# BLDCM.net
KiCad netlist of a schematic drawn in EAGLE
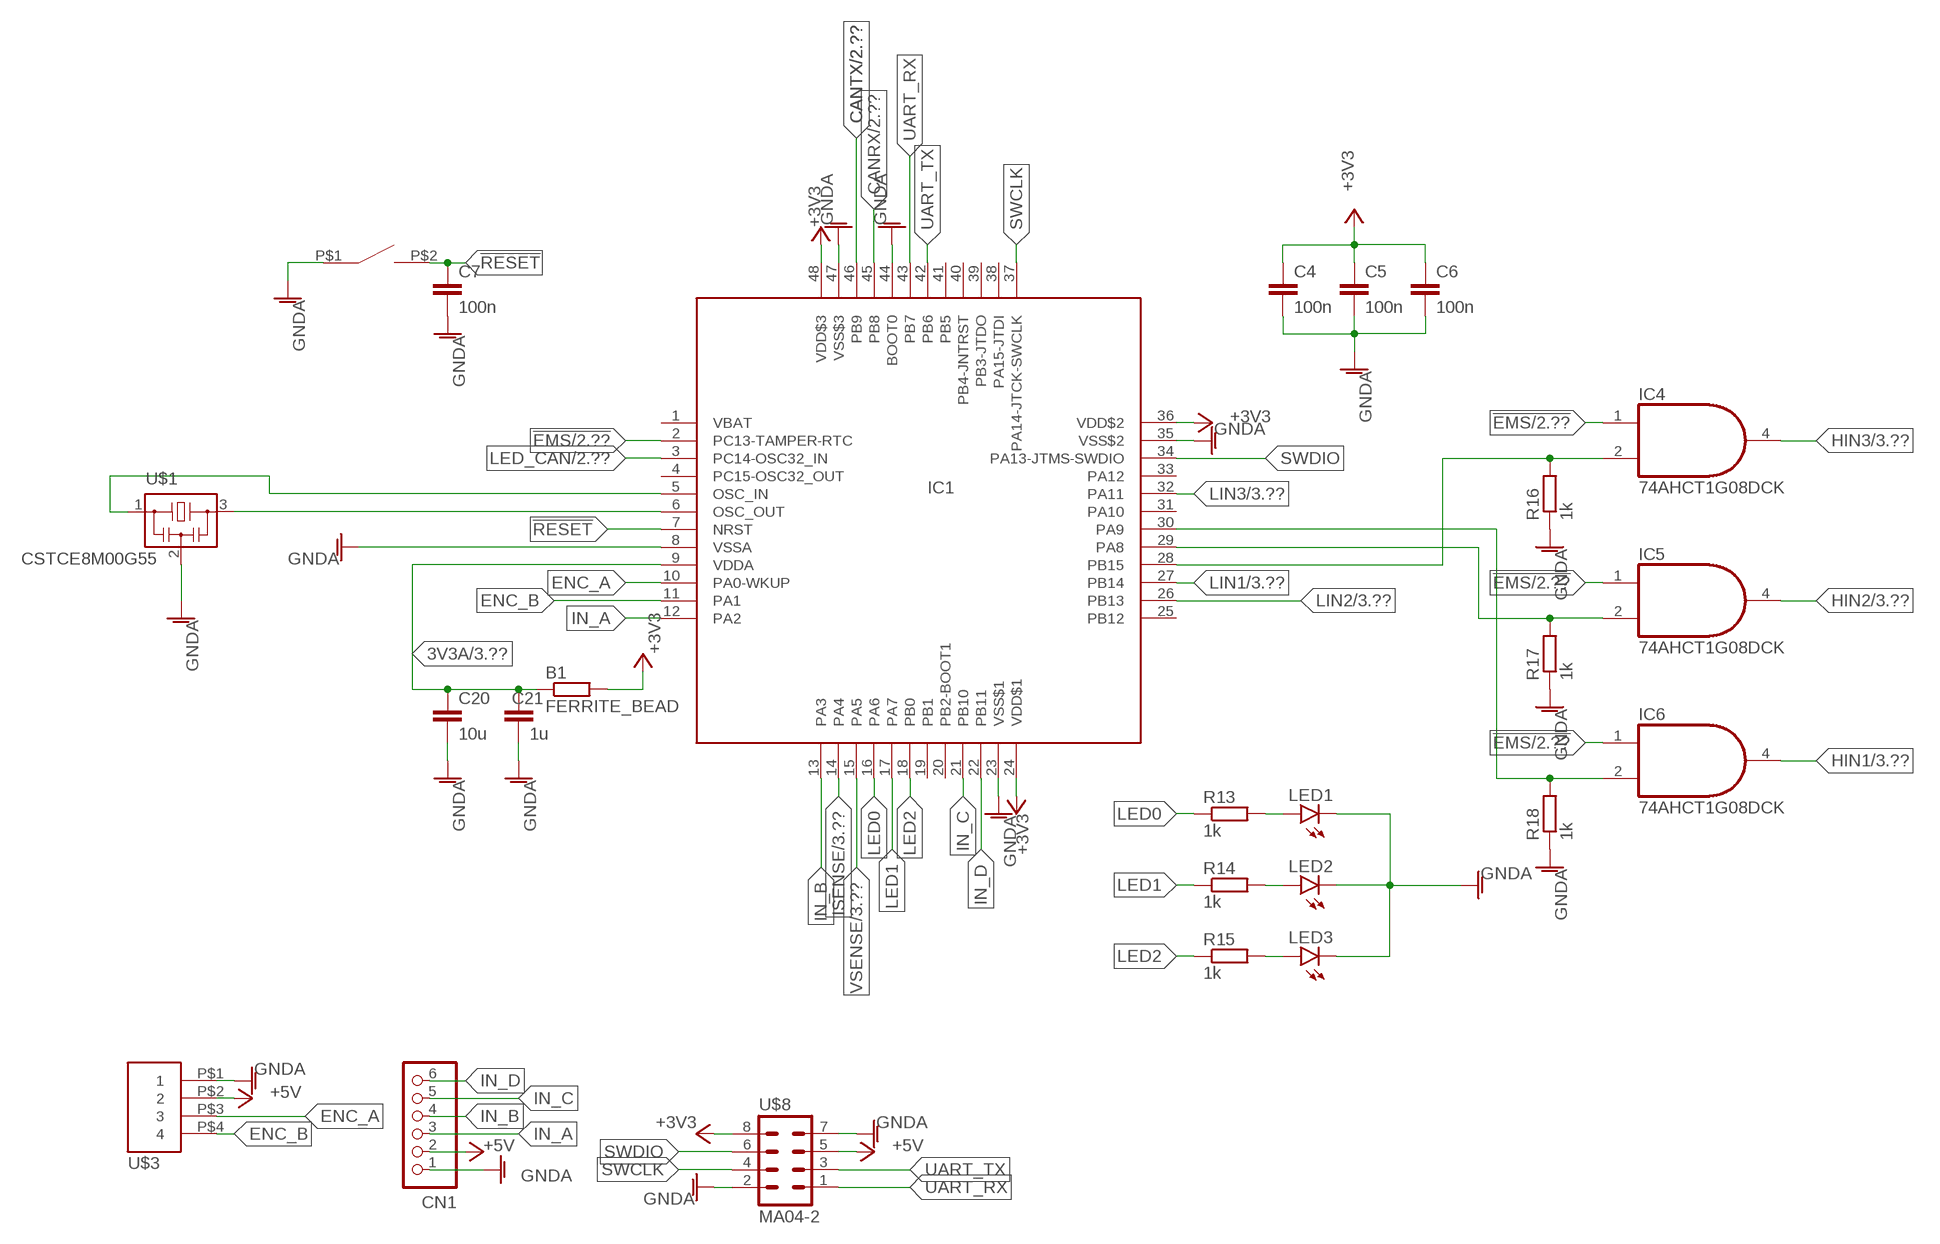
[diagram p0: schematic, sheet 1]
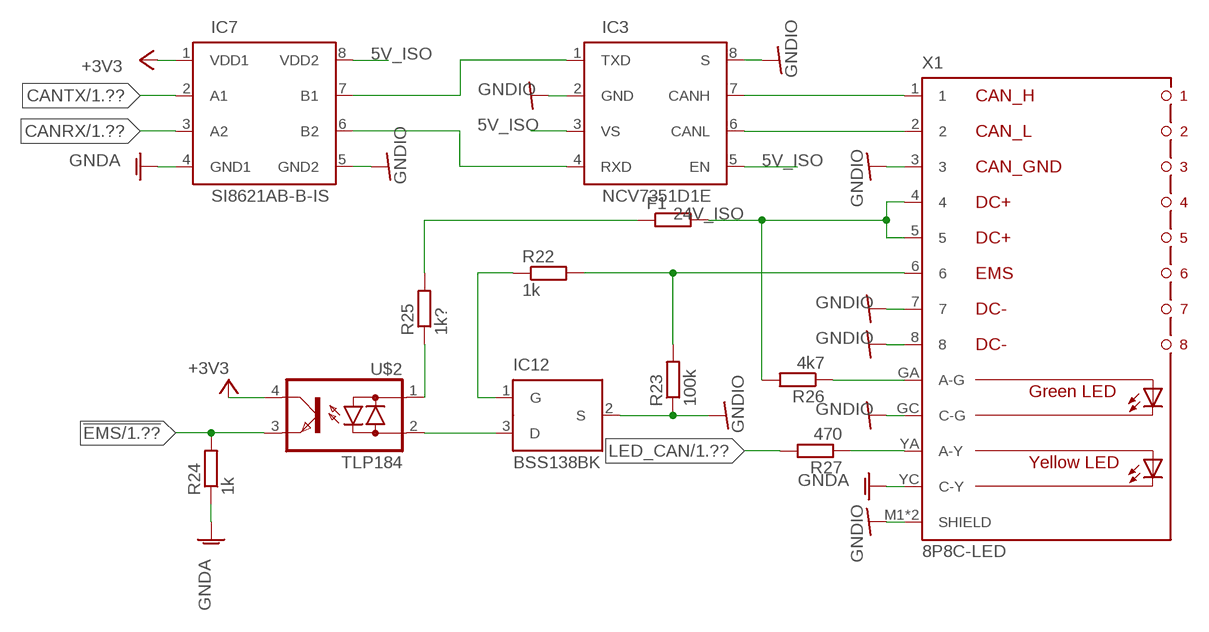
[diagram p1: schematic, sheet 2]
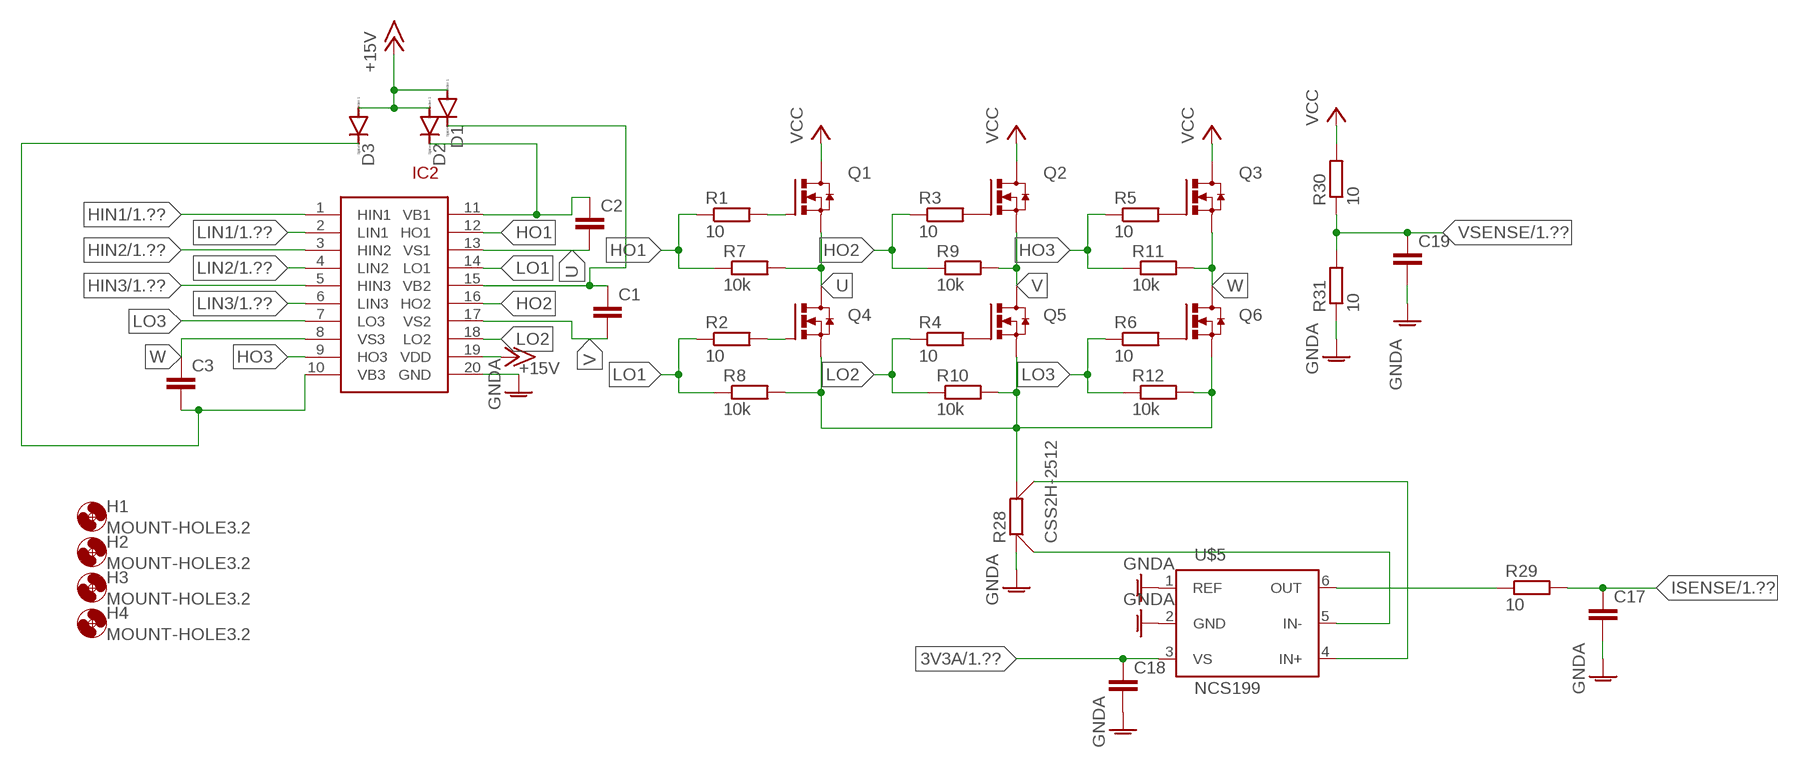
[diagram p2: schematic, sheet 3]
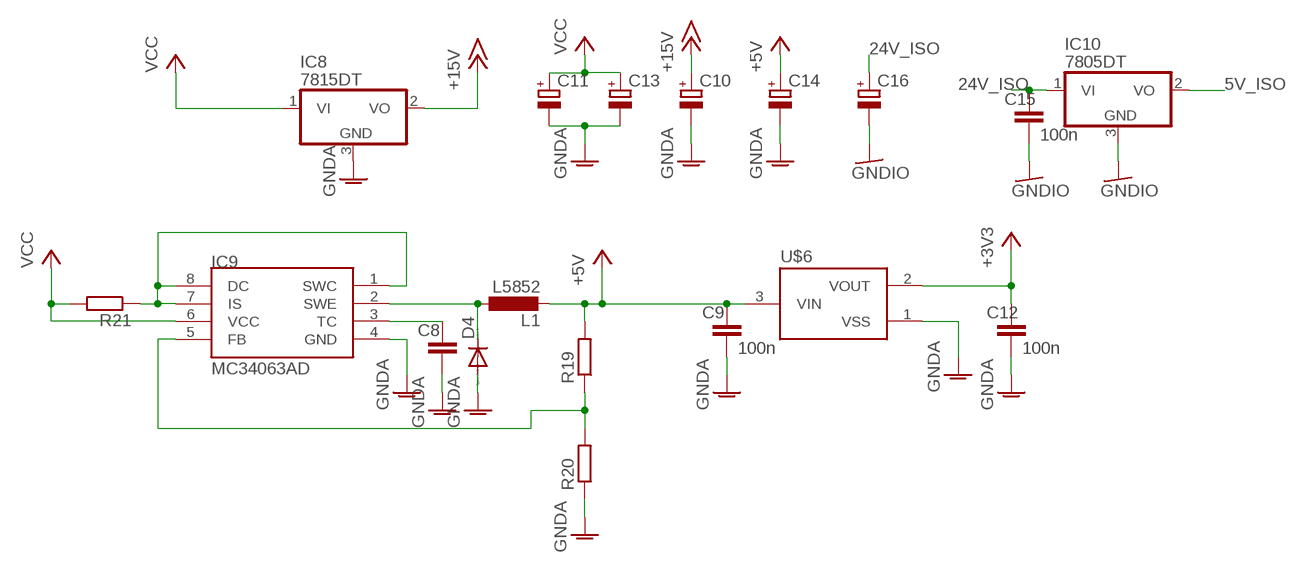
[diagram p3: schematic, sheet 4]

(export (version "E")
  (design (tool "Eeschema 10.0.6"))
  (components
    (comp (ref "C8")
      (value "C-EUC0603")
      (footprint "eagle-import:C0603")
      (libsource (lib "eagle-import") (part "C-EUC0603"))
    )
    (comp (ref "C9")
      (value "100n")
      (footprint "eagle-import:C0603")
      (libsource (lib "eagle-import") (part "C-EUC0603"))
    )
    (comp (ref "C10")
      (value "CPOL-EUE2.5-5")
      (footprint "eagle-import:E2,5-5")
      (libsource (lib "eagle-import") (part "CPOL-EUE2.5-5"))
    )
    (comp (ref "C11")
      (value "CPOL-EUE5-10.5")
      (footprint "eagle-import:E5-10,5")
      (libsource (lib "eagle-import") (part "CPOL-EUE5-10.5"))
    )
    (comp (ref "C12")
      (value "100n")
      (footprint "eagle-import:C0603")
      (libsource (lib "eagle-import") (part "C-EUC0603"))
    )
    (comp (ref "C13")
      (value "CPOL-EUE5-10.5")
      (footprint "eagle-import:E5-10,5")
      (libsource (lib "eagle-import") (part "CPOL-EUE5-10.5"))
    )
    (comp (ref "C14")
      (value "CPOL-EUE2.5-5")
      (footprint "eagle-import:E2,5-5")
      (libsource (lib "eagle-import") (part "CPOL-EUE2.5-5"))
    )
    (comp (ref "C15")
      (value "100n")
      (footprint "eagle-import:C0603")
      (libsource (lib "eagle-import") (part "C-EUC0603"))
    )
    (comp (ref "C16")
      (value "CPOL-EUE2.5-5")
      (footprint "eagle-import:E2,5-5")
      (libsource (lib "eagle-import") (part "CPOL-EUE2.5-5"))
    )
    (comp (ref "D4")
      (value "DIODE-SOD123")
      (footprint "eagle-import:SOD123")
      (libsource (lib "eagle-import") (part "mylib_DIODE-SOD123"))
    )
    (comp (ref "IC8")
      (value "7815DT")
      (footprint "eagle-import:TO252")
      (libsource (lib "eagle-import") (part "78DT24"))
    )
    (comp (ref "IC9")
      (value "MC34063AD")
      (footprint "eagle-import:SOIC8")
      (libsource (lib "eagle-import") (part "MC34063AD"))
    )
    (comp (ref "IC10")
      (value "7805DT")
      (footprint "eagle-import:TO252")
      (libsource (lib "eagle-import") (part "78DT24"))
    )
    (comp (ref "L1")
      (value "L5852")
      (footprint "eagle-import:L5852")
      (libsource (lib "eagle-import") (part "L5852"))
    )
    (comp (ref "R19")
      (value "R-EU_R0603")
      (footprint "eagle-import:R0603")
      (libsource (lib "eagle-import") (part "mylib_R-EU_R0603"))
    )
    (comp (ref "R20")
      (value "R-EU_R0603")
      (footprint "eagle-import:R0603")
      (libsource (lib "eagle-import") (part "mylib_R-EU_R0603"))
    )
    (comp (ref "R21")
      (value "R-EU_R0603")
      (footprint "eagle-import:R0603")
      (libsource (lib "eagle-import") (part "mylib_R-EU_R0603"))
    )
    (comp (ref "U$6")
      (value "XC6206")
      (footprint "eagle-import:SOT95P240X110-3")
      (libsource (lib "eagle-import") (part "XC6206"))
    )
    (comp (ref "B1")
      (value "FERRITE_BEAD")
      (footprint "eagle-import:R0603")
      (libsource (lib "eagle-import") (part "mylib_R-EU_R0603"))
    )
    (comp (ref "C4")
      (value "100n")
      (footprint "eagle-import:C0603")
      (libsource (lib "eagle-import") (part "rcl_334_C-EUC0603"))
    )
    (comp (ref "C5")
      (value "100n")
      (footprint "eagle-import:C0603")
      (libsource (lib "eagle-import") (part "rcl_334_C-EUC0603"))
    )
    (comp (ref "C6")
      (value "100n")
      (footprint "eagle-import:C0603")
      (libsource (lib "eagle-import") (part "rcl_334_C-EUC0603"))
    )
    (comp (ref "C7")
      (value "100n")
      (footprint "eagle-import:C0603")
      (libsource (lib "eagle-import") (part "rcl_334_C-EUC0603"))
    )
    (comp (ref "C20")
      (value "10u")
      (footprint "eagle-import:C0603")
      (libsource (lib "eagle-import") (part "rcl_334_C-EUC0603"))
    )
    (comp (ref "C21")
      (value "1u")
      (footprint "eagle-import:C0603")
      (libsource (lib "eagle-import") (part "rcl_334_C-EUC0603"))
    )
    (comp (ref "CN1")
      (value "S6B-XH-A")
      (footprint "eagle-import:S6B-XH-A")
      (libsource (lib "eagle-import") (part "S6B-XH-A"))
    )
    (comp (ref "IC1")
      (value "STM32F103C8")
      (footprint "eagle-import:LQFP48")
      (libsource (lib "eagle-import") (part "STM32F103C8"))
    )
    (comp (ref "IC4")
      (value "74AHCT1G08DCK")
      (footprint "eagle-import:SC70-5")
      (libsource (lib "eagle-import") (part "741G08DCKAHCT"))
    )
    (comp (ref "IC5")
      (value "74AHCT1G08DCK")
      (footprint "eagle-import:SC70-5")
      (libsource (lib "eagle-import") (part "741G08DCKAHCT"))
    )
    (comp (ref "IC6")
      (value "74AHCT1G08DCK")
      (footprint "eagle-import:SC70-5")
      (libsource (lib "eagle-import") (part "741G08DCKAHCT"))
    )
    (comp (ref "LED1")
      (value "LEDCHIP-LED0805")
      (footprint "eagle-import:CHIP-LED0805")
      (libsource (lib "eagle-import") (part "LEDCHIP-LED0805"))
    )
    (comp (ref "LED2")
      (value "LEDCHIP-LED0805")
      (footprint "eagle-import:CHIP-LED0805")
      (libsource (lib "eagle-import") (part "LEDCHIP-LED0805"))
    )
    (comp (ref "LED3")
      (value "LEDCHIP-LED0805")
      (footprint "eagle-import:CHIP-LED0805")
      (libsource (lib "eagle-import") (part "LEDCHIP-LED0805"))
    )
    (comp (ref "R13")
      (value "1k")
      (footprint "eagle-import:R0603")
      (libsource (lib "eagle-import") (part "mylib_R-EU_R0603"))
    )
    (comp (ref "R14")
      (value "1k")
      (footprint "eagle-import:R0603")
      (libsource (lib "eagle-import") (part "mylib_R-EU_R0603"))
    )
    (comp (ref "R15")
      (value "1k")
      (footprint "eagle-import:R0603")
      (libsource (lib "eagle-import") (part "mylib_R-EU_R0603"))
    )
    (comp (ref "R16")
      (value "1k")
      (footprint "eagle-import:R0603")
      (libsource (lib "eagle-import") (part "mylib_R-EU_R0603"))
    )
    (comp (ref "R17")
      (value "1k")
      (footprint "eagle-import:R0603")
      (libsource (lib "eagle-import") (part "mylib_R-EU_R0603"))
    )
    (comp (ref "R18")
      (value "1k")
      (footprint "eagle-import:R0603")
      (libsource (lib "eagle-import") (part "mylib_R-EU_R0603"))
    )
    (comp (ref "U$1")
      (value "CSTCE8M00G55")
      (footprint "eagle-import:CSTCE8M00G55")
      (libsource (lib "eagle-import") (part "CSTCE8M00G55"))
    )
    (comp (ref "U$3")
      (value "XH-4-SIDE")
      (footprint "eagle-import:CON-XH-4-SIDE")
      (libsource (lib "eagle-import") (part "XH-4-SIDE"))
    )
    (comp (ref "U$4")
      (value "SWITCH_TACTILETOP")
      (footprint "eagle-import:SWITCH_TACTILE_3X6")
      (libsource (lib "eagle-import") (part "SWITCH_TACTILETOP"))
    )
    (comp (ref "U$8")
      (value "MA04-2")
      (footprint "eagle-import:MA04-2W")
      (libsource (lib "eagle-import") (part "MA04-2"))
    )
    (comp (ref "F1")
      (value "R-EU_R1206")
      (footprint "eagle-import:R1206")
      (libsource (lib "eagle-import") (part "R-EU_R1206"))
    )
    (comp (ref "IC3")
      (value "NCV7351D1E")
      (footprint "eagle-import:SO08")
      (libsource (lib "eagle-import") (part "NCV7351D1E"))
    )
    (comp (ref "IC7")
      (value "SI8621AB-B-IS")
      (footprint "eagle-import:SO08")
      (libsource (lib "eagle-import") (part "SI8621AB-B-IS"))
    )
    (comp (ref "IC12")
      (value "BSS138BK")
      (footprint "eagle-import:SOT23")
      (fields (field (name "MF") "MAXIM") (field (name "MPN") "MAX6520EUR-T"))
      (libsource (lib "eagle-import") (part "BSS138BK"))
    )
    (comp (ref "R22")
      (value "1k")
      (footprint "eagle-import:R0603")
      (libsource (lib "eagle-import") (part "mylib_R-EU_R0603"))
    )
    (comp (ref "R23")
      (value "100k")
      (footprint "eagle-import:R0603")
      (libsource (lib "eagle-import") (part "mylib_R-EU_R0603"))
    )
    (comp (ref "R24")
      (value "1k")
      (footprint "eagle-import:R0603")
      (libsource (lib "eagle-import") (part "mylib_R-EU_R0603"))
    )
    (comp (ref "R25")
      (value "1k?")
      (footprint "eagle-import:R0603")
      (libsource (lib "eagle-import") (part "mylib_R-EU_R0603"))
    )
    (comp (ref "R26")
      (value "4k7")
      (footprint "eagle-import:R0603")
      (libsource (lib "eagle-import") (part "mylib_R-EU_R0603"))
    )
    (comp (ref "R27")
      (value "470")
      (footprint "eagle-import:R0603")
      (libsource (lib "eagle-import") (part "mylib_R-EU_R0603"))
    )
    (comp (ref "U$2")
      (value "TLP184")
      (footprint "eagle-import:11-4M1S")
      (libsource (lib "eagle-import") (part "TLP184"))
    )
    (comp (ref "X1")
      (value "8P8C-LED")
      (footprint "eagle-import:8P8C-LED")
      (libsource (lib "eagle-import") (part "8P8C-LED"))
    )
    (comp (ref "C1")
      (value "C-EUC0603")
      (footprint "eagle-import:C0603")
      (libsource (lib "eagle-import") (part "rcl_334_C-EUC0603"))
    )
    (comp (ref "C2")
      (value "C-EUC0603")
      (footprint "eagle-import:C0603")
      (libsource (lib "eagle-import") (part "rcl_334_C-EUC0603"))
    )
    (comp (ref "C3")
      (value "C-EUC0603")
      (footprint "eagle-import:C0603")
      (libsource (lib "eagle-import") (part "rcl_334_C-EUC0603"))
    )
    (comp (ref "C17")
      (value "C-EUC0603")
      (footprint "eagle-import:C0603")
      (libsource (lib "eagle-import") (part "rcl_334_C-EUC0603"))
    )
    (comp (ref "C18")
      (value "C-EUC0603")
      (footprint "eagle-import:C0603")
      (libsource (lib "eagle-import") (part "rcl_334_C-EUC0603"))
    )
    (comp (ref "C19")
      (value "C-EUC0603")
      (footprint "eagle-import:C0603")
      (libsource (lib "eagle-import") (part "rcl_334_C-EUC0603"))
    )
    (comp (ref "D1")
      (value "DIODE-SOD323-R")
      (footprint "eagle-import:SOD323-R")
      (libsource (lib "eagle-import") (part "DIODE-SOD323-R"))
    )
    (comp (ref "D2")
      (value "DIODE-SOD323-R")
      (footprint "eagle-import:SOD323-R")
      (libsource (lib "eagle-import") (part "DIODE-SOD323-R"))
    )
    (comp (ref "D3")
      (value "DIODE-SOD323-R")
      (footprint "eagle-import:SOD323-R")
      (libsource (lib "eagle-import") (part "DIODE-SOD323-R"))
    )
    (comp (ref "H1")
      (value "MOUNT-HOLE3.2")
      (footprint "eagle-import:3,2")
      (libsource (lib "eagle-import") (part "MOUNT-HOLE3.2"))
    )
    (comp (ref "H2")
      (value "MOUNT-HOLE3.2")
      (footprint "eagle-import:3,2")
      (libsource (lib "eagle-import") (part "MOUNT-HOLE3.2"))
    )
    (comp (ref "H3")
      (value "MOUNT-HOLE3.2")
      (footprint "eagle-import:3,2")
      (libsource (lib "eagle-import") (part "MOUNT-HOLE3.2"))
    )
    (comp (ref "H4")
      (value "MOUNT-HOLE3.2")
      (footprint "eagle-import:3,2")
      (libsource (lib "eagle-import") (part "MOUNT-HOLE3.2"))
    )
    (comp (ref "IC2")
      (value "FAN7888MX")
      (footprint "eagle-import:SOIC20S")
      (libsource (lib "eagle-import") (part "FAN7888MX"))
    )
    (comp (ref "Q1")
      (value "N-MOSFET-")
      (footprint "eagle-import:SOT669")
      (libsource (lib "eagle-import") (part "N-MOSFET-"))
    )
    (comp (ref "Q2")
      (value "N-MOSFET-")
      (footprint "eagle-import:SOT669")
      (libsource (lib "eagle-import") (part "N-MOSFET-"))
    )
    (comp (ref "Q3")
      (value "N-MOSFET-")
      (footprint "eagle-import:SOT669")
      (libsource (lib "eagle-import") (part "N-MOSFET-"))
    )
    (comp (ref "Q4")
      (value "N-MOSFET-")
      (footprint "eagle-import:SOT669")
      (libsource (lib "eagle-import") (part "N-MOSFET-"))
    )
    (comp (ref "Q5")
      (value "N-MOSFET-")
      (footprint "eagle-import:SOT669")
      (libsource (lib "eagle-import") (part "N-MOSFET-"))
    )
    (comp (ref "Q6")
      (value "N-MOSFET-")
      (footprint "eagle-import:SOT669")
      (libsource (lib "eagle-import") (part "N-MOSFET-"))
    )
    (comp (ref "R1")
      (value "10")
      (footprint "eagle-import:R0603")
      (libsource (lib "eagle-import") (part "mylib_R-EU_R0603"))
    )
    (comp (ref "R2")
      (value "10")
      (footprint "eagle-import:R0603")
      (libsource (lib "eagle-import") (part "mylib_R-EU_R0603"))
    )
    (comp (ref "R3")
      (value "10")
      (footprint "eagle-import:R0603")
      (libsource (lib "eagle-import") (part "mylib_R-EU_R0603"))
    )
    (comp (ref "R4")
      (value "10")
      (footprint "eagle-import:R0603")
      (libsource (lib "eagle-import") (part "mylib_R-EU_R0603"))
    )
    (comp (ref "R5")
      (value "10")
      (footprint "eagle-import:R0603")
      (libsource (lib "eagle-import") (part "mylib_R-EU_R0603"))
    )
    (comp (ref "R6")
      (value "10")
      (footprint "eagle-import:R0603")
      (libsource (lib "eagle-import") (part "mylib_R-EU_R0603"))
    )
    (comp (ref "R7")
      (value "10k")
      (footprint "eagle-import:R0603")
      (libsource (lib "eagle-import") (part "mylib_R-EU_R0603"))
    )
    (comp (ref "R8")
      (value "10k")
      (footprint "eagle-import:R0603")
      (libsource (lib "eagle-import") (part "mylib_R-EU_R0603"))
    )
    (comp (ref "R9")
      (value "10k")
      (footprint "eagle-import:R0603")
      (libsource (lib "eagle-import") (part "mylib_R-EU_R0603"))
    )
    (comp (ref "R10")
      (value "10k")
      (footprint "eagle-import:R0603")
      (libsource (lib "eagle-import") (part "mylib_R-EU_R0603"))
    )
    (comp (ref "R11")
      (value "10k")
      (footprint "eagle-import:R0603")
      (libsource (lib "eagle-import") (part "mylib_R-EU_R0603"))
    )
    (comp (ref "R12")
      (value "10k")
      (footprint "eagle-import:R0603")
      (libsource (lib "eagle-import") (part "mylib_R-EU_R0603"))
    )
    (comp (ref "R28")
      (value "CSS2H-2512")
      (footprint "eagle-import:CSS2H-2512")
      (libsource (lib "eagle-import") (part "CSS2H-2512"))
    )
    (comp (ref "R29")
      (value "10")
      (footprint "eagle-import:R0603")
      (libsource (lib "eagle-import") (part "mylib_R-EU_R0603"))
    )
    (comp (ref "R30")
      (value "10")
      (footprint "eagle-import:R0603")
      (libsource (lib "eagle-import") (part "mylib_R-EU_R0603"))
    )
    (comp (ref "R31")
      (value "10")
      (footprint "eagle-import:R0603")
      (libsource (lib "eagle-import") (part "mylib_R-EU_R0603"))
    )
    (comp (ref "U$5")
      (value "NCS199")
      (footprint "eagle-import:SOT65P210X110-6")
      (libsource (lib "eagle-import") (part "NCS199"))
    )
  )
  (nets
    (net (code "1") (name "+3V3") (class "Default")
      (node (ref "B1") (pin "2") (pinfunction "2_2") (pintype "passive"))
      (node (ref "C12") (pin "1") (pinfunction "1_1") (pintype "passive"))
      (node (ref "C4") (pin "1") (pinfunction "1_1") (pintype "passive"))
      (node (ref "C5") (pin "1") (pinfunction "1_1") (pintype "passive"))
      (node (ref "C6") (pin "1") (pinfunction "1_1") (pintype "passive"))
      (node (ref "IC1") (pin "24") (pinfunction "VDD$1_24") (pintype "passive"))
      (node (ref "IC1") (pin "36") (pinfunction "VDD$2_36") (pintype "passive"))
      (node (ref "IC1") (pin "48") (pinfunction "VDD$3_48") (pintype "passive"))
      (node (ref "IC7") (pin "1") (pinfunction "VDD1_1") (pintype "power_in"))
      (node (ref "U$2") (pin "4") (pinfunction "C_4") (pintype "passive"))
      (node (ref "U$6") (pin "2") (pinfunction "VOUT_2") (pintype "bidirectional"))
      (node (ref "U$8") (pin "8") (pinfunction "8_8") (pintype "passive"))
    )
    (net (code "2") (name "+5V") (class "Default")
      (node (ref "C14") (pin "+") (pinfunction "+_+") (pintype "passive"))
      (node (ref "C9") (pin "1") (pinfunction "1_1") (pintype "passive"))
      (node (ref "CN1") (pin "2") (pinfunction "2_2") (pintype "passive"))
      (node (ref "L1") (pin "P$2") (pinfunction "2_P$2") (pintype "passive"))
      (node (ref "R19") (pin "2") (pinfunction "2_2") (pintype "passive"))
      (node (ref "U$3") (pin "P$2") (pinfunction "2_P$2") (pintype "bidirectional"))
      (node (ref "U$6") (pin "3") (pinfunction "VIN_3") (pintype "bidirectional"))
      (node (ref "U$8") (pin "5") (pinfunction "5_5") (pintype "passive"))
    )
    (net (code "3") (name "+15V") (class "Default")
      (node (ref "C10") (pin "+") (pinfunction "+_+") (pintype "passive"))
      (node (ref "D1") (pin "A") (pinfunction "A_A") (pintype "passive"))
      (node (ref "D2") (pin "A") (pinfunction "A_A") (pintype "passive"))
      (node (ref "D3") (pin "A") (pinfunction "A_A") (pintype "passive"))
      (node (ref "IC2") (pin "19") (pinfunction "VDD_19") (pintype "power_in"))
      (node (ref "IC8") (pin "2") (pinfunction "VO_2") (pintype "passive"))
    )
    (net (code "4") (name "3V3A") (class "Default")
      (node (ref "B1") (pin "1") (pinfunction "1_1") (pintype "passive"))
      (node (ref "C18") (pin "1") (pinfunction "1_1") (pintype "passive"))
      (node (ref "C20") (pin "1") (pinfunction "1_1") (pintype "passive"))
      (node (ref "C21") (pin "1") (pinfunction "1_1") (pintype "passive"))
      (node (ref "IC1") (pin "9") (pinfunction "VDDA_9") (pintype "bidirectional"))
      (node (ref "U$5") (pin "3") (pinfunction "VS_3") (pintype "power_in"))
    )
    (net (code "5") (name "5V_ISO") (class "Default")
      (node (ref "IC10") (pin "2") (pinfunction "VO_2") (pintype "passive"))
      (node (ref "IC3") (pin "3") (pinfunction "VS_3") (pintype "power_in"))
      (node (ref "IC3") (pin "5") (pinfunction "EN_5") (pintype "input"))
      (node (ref "IC7") (pin "8") (pinfunction "VDD2_8") (pintype "power_in"))
    )
    (net (code "6") (name "24V_ISO") (class "Default")
      (node (ref "C15") (pin "1") (pinfunction "1_1") (pintype "passive"))
      (node (ref "C16") (pin "+") (pinfunction "+_+") (pintype "passive"))
      (node (ref "F1") (pin "1") (pinfunction "1_1") (pintype "passive"))
      (node (ref "IC10") (pin "1") (pinfunction "VI_1") (pintype "input"))
      (node (ref "R25") (pin "2") (pinfunction "2_2") (pintype "passive"))
    )
    (net (code "7") (name "CANRX") (class "Default")
      (node (ref "IC1") (pin "45") (pinfunction "PB8_45") (pintype "bidirectional"))
      (node (ref "IC7") (pin "3") (pinfunction "A2_3") (pintype "output"))
    )
    (net (code "8") (name "CANTX") (class "Default")
      (node (ref "IC1") (pin "46") (pinfunction "PB9_46") (pintype "bidirectional"))
      (node (ref "IC7") (pin "2") (pinfunction "A1_2") (pintype "input"))
    )
    (net (code "9") (name "ENC_A") (class "Default")
      (node (ref "IC1") (pin "10") (pinfunction "PA0-WKUP_10") (pintype "bidirectional"))
      (node (ref "U$3") (pin "P$3") (pinfunction "3_P$3") (pintype "bidirectional"))
    )
    (net (code "10") (name "ENC_B") (class "Default")
      (node (ref "IC1") (pin "11") (pinfunction "PA1_11") (pintype "bidirectional"))
      (node (ref "U$3") (pin "P$4") (pinfunction "4_P$4") (pintype "bidirectional"))
    )
    (net (code "11") (name "GNDA") (class "Default")
      (node (ref "C10") (pin "-") (pinfunction "-_-") (pintype "passive"))
      (node (ref "C11") (pin "-") (pinfunction "-_-") (pintype "passive"))
      (node (ref "C12") (pin "2") (pinfunction "2_2") (pintype "passive"))
      (node (ref "C13") (pin "-") (pinfunction "-_-") (pintype "passive"))
      (node (ref "C14") (pin "-") (pinfunction "-_-") (pintype "passive"))
      (node (ref "C17") (pin "2") (pinfunction "2_2") (pintype "passive"))
      (node (ref "C18") (pin "2") (pinfunction "2_2") (pintype "passive"))
      (node (ref "C19") (pin "2") (pinfunction "2_2") (pintype "passive"))
      (node (ref "C20") (pin "2") (pinfunction "2_2") (pintype "passive"))
      (node (ref "C21") (pin "2") (pinfunction "2_2") (pintype "passive"))
      (node (ref "C4") (pin "2") (pinfunction "2_2") (pintype "passive"))
      (node (ref "C5") (pin "2") (pinfunction "2_2") (pintype "passive"))
      (node (ref "C6") (pin "2") (pinfunction "2_2") (pintype "passive"))
      (node (ref "C7") (pin "2") (pinfunction "2_2") (pintype "passive"))
      (node (ref "C8") (pin "2") (pinfunction "2_2") (pintype "passive"))
      (node (ref "C9") (pin "2") (pinfunction "2_2") (pintype "passive"))
      (node (ref "CN1") (pin "1") (pinfunction "1_1") (pintype "passive"))
      (node (ref "D4") (pin "A") (pinfunction "A_A") (pintype "passive"))
      (node (ref "IC1") (pin "23") (pinfunction "VSS$1_23") (pintype "passive"))
      (node (ref "IC1") (pin "35") (pinfunction "VSS$2_35") (pintype "passive"))
      (node (ref "IC1") (pin "44") (pinfunction "BOOT0_44") (pintype "input"))
      (node (ref "IC1") (pin "47") (pinfunction "VSS$3_47") (pintype "passive"))
      (node (ref "IC1") (pin "8") (pinfunction "VSSA_8") (pintype "bidirectional"))
      (node (ref "IC2") (pin "20") (pinfunction "GND_20") (pintype "power_in"))
      (node (ref "IC7") (pin "4") (pinfunction "GND1_4") (pintype "power_in"))
      (node (ref "IC8") (pin "3") (pinfunction "GND_3") (pintype "passive"))
      (node (ref "IC9") (pin "4") (pinfunction "GND_4") (pintype "passive"))
      (node (ref "LED1") (pin "C") (pinfunction "C_C") (pintype "passive"))
      (node (ref "LED2") (pin "C") (pinfunction "C_C") (pintype "passive"))
      (node (ref "LED3") (pin "C") (pinfunction "C_C") (pintype "passive"))
      (node (ref "R16") (pin "1") (pinfunction "1_1") (pintype "passive"))
      (node (ref "R17") (pin "1") (pinfunction "1_1") (pintype "passive"))
      (node (ref "R18") (pin "1") (pinfunction "1_1") (pintype "passive"))
      (node (ref "R20") (pin "1") (pinfunction "1_1") (pintype "passive"))
      (node (ref "R24") (pin "1") (pinfunction "1_1") (pintype "passive"))
      (node (ref "R28") (pin "1$1") (pinfunction "1_1$1") (pintype "passive"))
      (node (ref "R28") (pin "1$2") (pinfunction "1_1$2") (pintype "passive"))
      (node (ref "R31") (pin "1") (pinfunction "1_1") (pintype "passive"))
      (node (ref "U$1") (pin "2") (pinfunction "2_2") (pintype "passive"))
      (node (ref "U$3") (pin "P$1") (pinfunction "1_P$1") (pintype "bidirectional"))
      (node (ref "U$4") (pin "P$1") (pinfunction "1_P$1") (pintype "bidirectional"))
      (node (ref "U$5") (pin "1") (pinfunction "REF_1") (pintype "power_in"))
      (node (ref "U$5") (pin "2") (pinfunction "GND_2") (pintype "power_in"))
      (node (ref "U$6") (pin "1") (pinfunction "VSS_1") (pintype "bidirectional"))
      (node (ref "U$8") (pin "2") (pinfunction "2_2") (pintype "passive"))
      (node (ref "U$8") (pin "7") (pinfunction "7_7") (pintype "passive"))
      (node (ref "X1") (pin "YC") (pinfunction "C-Y_YC") (pintype "passive"))
    )
    (net (code "12") (name "GNDIO") (class "Default")
      (node (ref "C15") (pin "2") (pinfunction "2_2") (pintype "passive"))
      (node (ref "C16") (pin "-") (pinfunction "-_-") (pintype "passive"))
      (node (ref "IC10") (pin "3") (pinfunction "GND_3") (pintype "passive"))
      (node (ref "IC12") (pin "2") (pinfunction "S_2") (pintype "output"))
      (node (ref "IC3") (pin "2") (pinfunction "GND_2") (pintype "power_in"))
      (node (ref "IC3") (pin "8") (pinfunction "S_8") (pintype "input"))
      (node (ref "IC7") (pin "5") (pinfunction "GND2_5") (pintype "power_in"))
      (node (ref "R23") (pin "1") (pinfunction "1_1") (pintype "passive"))
      (node (ref "X1") (pin "3") (pinfunction "3_3") (pintype "input"))
      (node (ref "X1") (pin "7") (pinfunction "7_7") (pintype "input"))
      (node (ref "X1") (pin "8") (pinfunction "8_8") (pintype "input"))
      (node (ref "X1") (pin "GC") (pinfunction "C-G_GC") (pintype "passive"))
      (node (ref "X1") (pin "M1") (pinfunction "SHIELD_M1") (pintype "passive"))
      (node (ref "X1") (pin "M2") (pinfunction "SHIELD_M2") (pintype "passive"))
    )
    (net (code "13") (name "HIN1") (class "Default")
      (node (ref "IC2") (pin "1") (pinfunction "HIN1_1") (pintype "bidirectional"))
      (node (ref "IC6") (pin "4") (pinfunction "O_4") (pintype "output"))
    )
    (net (code "14") (name "HIN2") (class "Default")
      (node (ref "IC2") (pin "3") (pinfunction "HIN2_3") (pintype "bidirectional"))
      (node (ref "IC5") (pin "4") (pinfunction "O_4") (pintype "output"))
    )
    (net (code "15") (name "HIN3") (class "Default")
      (node (ref "IC2") (pin "5") (pinfunction "HIN3_5") (pintype "bidirectional"))
      (node (ref "IC4") (pin "4") (pinfunction "O_4") (pintype "output"))
    )
    (net (code "16") (name "HO1") (class "Default")
      (node (ref "IC2") (pin "12") (pinfunction "HO1_12") (pintype "bidirectional"))
      (node (ref "R1") (pin "1") (pinfunction "1_1") (pintype "passive"))
      (node (ref "R7") (pin "1") (pinfunction "1_1") (pintype "passive"))
    )
    (net (code "17") (name "HO2") (class "Default")
      (node (ref "IC2") (pin "16") (pinfunction "HO2_16") (pintype "bidirectional"))
      (node (ref "R3") (pin "1") (pinfunction "1_1") (pintype "passive"))
      (node (ref "R9") (pin "1") (pinfunction "1_1") (pintype "passive"))
    )
    (net (code "18") (name "HO3") (class "Default")
      (node (ref "IC2") (pin "9") (pinfunction "HO3_9") (pintype "bidirectional"))
      (node (ref "R11") (pin "1") (pinfunction "1_1") (pintype "passive"))
      (node (ref "R5") (pin "1") (pinfunction "1_1") (pintype "passive"))
    )
    (net (code "19") (name "IN_A") (class "Default")
      (node (ref "CN1") (pin "3") (pinfunction "3_3") (pintype "passive"))
      (node (ref "IC1") (pin "12") (pinfunction "PA2_12") (pintype "bidirectional"))
    )
    (net (code "20") (name "IN_B") (class "Default")
      (node (ref "CN1") (pin "4") (pinfunction "4_4") (pintype "passive"))
      (node (ref "IC1") (pin "13") (pinfunction "PA3_13") (pintype "bidirectional"))
    )
    (net (code "21") (name "IN_C") (class "Default")
      (node (ref "CN1") (pin "5") (pinfunction "5_5") (pintype "passive"))
      (node (ref "IC1") (pin "21") (pinfunction "PB10_21") (pintype "bidirectional"))
    )
    (net (code "22") (name "IN_D") (class "Default")
      (node (ref "CN1") (pin "6") (pinfunction "6_6") (pintype "passive"))
      (node (ref "IC1") (pin "22") (pinfunction "PB11_22") (pintype "bidirectional"))
    )
    (net (code "23") (name "ISENSE") (class "Default")
      (node (ref "C17") (pin "1") (pinfunction "1_1") (pintype "passive"))
      (node (ref "IC1") (pin "14") (pinfunction "PA4_14") (pintype "bidirectional"))
      (node (ref "R29") (pin "2") (pinfunction "2_2") (pintype "passive"))
    )
    (net (code "24") (name "LED0") (class "Default")
      (node (ref "IC1") (pin "16") (pinfunction "PA6_16") (pintype "bidirectional"))
      (node (ref "R13") (pin "1") (pinfunction "1_1") (pintype "passive"))
    )
    (net (code "25") (name "LED1") (class "Default")
      (node (ref "IC1") (pin "17") (pinfunction "PA7_17") (pintype "bidirectional"))
      (node (ref "R14") (pin "1") (pinfunction "1_1") (pintype "passive"))
    )
    (net (code "26") (name "LED2") (class "Default")
      (node (ref "IC1") (pin "18") (pinfunction "PB0_18") (pintype "bidirectional"))
      (node (ref "R15") (pin "1") (pinfunction "1_1") (pintype "passive"))
    )
    (net (code "27") (name "LED_CAN") (class "Default")
      (node (ref "IC1") (pin "3") (pinfunction "PC14-OSC32_IN_3") (pintype "bidirectional"))
      (node (ref "R27") (pin "2") (pinfunction "2_2") (pintype "passive"))
    )
    (net (code "28") (name "LIN1") (class "Default")
      (node (ref "IC1") (pin "27") (pinfunction "PB14_27") (pintype "bidirectional"))
      (node (ref "IC2") (pin "2") (pinfunction "LIN1_2") (pintype "bidirectional"))
    )
    (net (code "29") (name "LIN2") (class "Default")
      (node (ref "IC1") (pin "26") (pinfunction "PB13_26") (pintype "bidirectional"))
      (node (ref "IC2") (pin "4") (pinfunction "LIN2_4") (pintype "bidirectional"))
    )
    (net (code "30") (name "LIN3") (class "Default")
      (node (ref "IC1") (pin "32") (pinfunction "PA11_32") (pintype "bidirectional"))
      (node (ref "IC2") (pin "6") (pinfunction "LIN3_6") (pintype "bidirectional"))
    )
    (net (code "31") (name "LO1") (class "Default")
      (node (ref "IC2") (pin "14") (pinfunction "LO1_14") (pintype "bidirectional"))
      (node (ref "R2") (pin "1") (pinfunction "1_1") (pintype "passive"))
      (node (ref "R8") (pin "1") (pinfunction "1_1") (pintype "passive"))
    )
    (net (code "32") (name "LO2") (class "Default")
      (node (ref "IC2") (pin "18") (pinfunction "LO2_18") (pintype "bidirectional"))
      (node (ref "R10") (pin "1") (pinfunction "1_1") (pintype "passive"))
      (node (ref "R4") (pin "1") (pinfunction "1_1") (pintype "passive"))
    )
    (net (code "33") (name "LO3") (class "Default")
      (node (ref "IC2") (pin "7") (pinfunction "LO3_7") (pintype "bidirectional"))
      (node (ref "R12") (pin "1") (pinfunction "1_1") (pintype "passive"))
      (node (ref "R6") (pin "1") (pinfunction "1_1") (pintype "passive"))
    )
    (net (code "34") (name "Net-(F1-Pad2)") (class "Default")
      (node (ref "F1") (pin "2") (pinfunction "2_2") (pintype "passive"))
      (node (ref "R26") (pin "2") (pinfunction "2_2") (pintype "passive"))
      (node (ref "X1") (pin "4") (pinfunction "4_4") (pintype "input"))
      (node (ref "X1") (pin "5") (pinfunction "5_5") (pintype "input"))
    )
    (net (code "35") (name "Net-(IC1-OSC_IN)") (class "Default")
      (node (ref "IC1") (pin "5") (pinfunction "OSC_IN_5") (pintype "input"))
      (node (ref "U$1") (pin "1") (pinfunction "1_1") (pintype "passive"))
    )
    (net (code "36") (name "Net-(IC1-OSC_OUT)") (class "Default")
      (node (ref "IC1") (pin "6") (pinfunction "OSC_OUT_6") (pintype "output"))
      (node (ref "U$1") (pin "3") (pinfunction "3_3") (pintype "passive"))
    )
    (net (code "37") (name "Net-(IC1-PA8)") (class "Default")
      (node (ref "IC1") (pin "29") (pinfunction "PA8_29") (pintype "bidirectional"))
      (node (ref "IC5") (pin "2") (pinfunction "I1_2") (pintype "input"))
      (node (ref "R17") (pin "2") (pinfunction "2_2") (pintype "passive"))
    )
    (net (code "38") (name "Net-(IC1-PA9)") (class "Default")
      (node (ref "IC1") (pin "30") (pinfunction "PA9_30") (pintype "bidirectional"))
      (node (ref "IC6") (pin "2") (pinfunction "I1_2") (pintype "input"))
      (node (ref "R18") (pin "2") (pinfunction "2_2") (pintype "passive"))
    )
    (net (code "39") (name "Net-(IC1-PB15)") (class "Default")
      (node (ref "IC1") (pin "28") (pinfunction "PB15_28") (pintype "bidirectional"))
      (node (ref "IC4") (pin "2") (pinfunction "I1_2") (pintype "input"))
      (node (ref "R16") (pin "2") (pinfunction "2_2") (pintype "passive"))
    )
    (net (code "40") (name "Net-(IC2-VB1)") (class "Default")
      (node (ref "C2") (pin "1") (pinfunction "1_1") (pintype "passive"))
      (node (ref "D2") (pin "C") (pinfunction "C_C") (pintype "passive"))
      (node (ref "IC2") (pin "11") (pinfunction "VB1_11") (pintype "bidirectional"))
    )
    (net (code "41") (name "Net-(IC2-VB2)") (class "Default")
      (node (ref "C1") (pin "1") (pinfunction "1_1") (pintype "passive"))
      (node (ref "D1") (pin "C") (pinfunction "C_C") (pintype "passive"))
      (node (ref "IC2") (pin "15") (pinfunction "VB2_15") (pintype "bidirectional"))
    )
    (net (code "42") (name "Net-(IC2-VB3)") (class "Default")
      (node (ref "C3") (pin "2") (pinfunction "2_2") (pintype "passive"))
      (node (ref "D3") (pin "C") (pinfunction "C_C") (pintype "passive"))
      (node (ref "IC2") (pin "10") (pinfunction "VB3_10") (pintype "bidirectional"))
    )
    (net (code "43") (name "Net-(IC3-CANH)") (class "Default")
      (node (ref "IC3") (pin "7") (pinfunction "CANH_7") (pintype "output"))
      (node (ref "X1") (pin "1") (pinfunction "1_1") (pintype "input"))
    )
    (net (code "44") (name "Net-(IC3-CANL)") (class "Default")
      (node (ref "IC3") (pin "6") (pinfunction "CANL_6") (pintype "output"))
      (node (ref "X1") (pin "2") (pinfunction "2_2") (pintype "input"))
    )
    (net (code "45") (name "Net-(IC3-RXD)") (class "Default")
      (node (ref "IC3") (pin "4") (pinfunction "RXD_4") (pintype "output"))
      (node (ref "IC7") (pin "6") (pinfunction "B2_6") (pintype "output"))
    )
    (net (code "46") (name "Net-(IC3-TXD)") (class "Default")
      (node (ref "IC3") (pin "1") (pinfunction "TXD_1") (pintype "input"))
      (node (ref "IC7") (pin "7") (pinfunction "B1_7") (pintype "output"))
    )
    (net (code "47") (name "Net-(IC9-DC)") (class "Default")
      (node (ref "IC9") (pin "1") (pinfunction "SWC_1") (pintype "passive"))
      (node (ref "IC9") (pin "7") (pinfunction "IS_7") (pintype "passive"))
      (node (ref "IC9") (pin "8") (pinfunction "DC_8") (pintype "passive"))
      (node (ref "R21") (pin "1") (pinfunction "1_1") (pintype "passive"))
    )
    (net (code "48") (name "Net-(IC9-FB)") (class "Default")
      (node (ref "IC9") (pin "5") (pinfunction "FB_5") (pintype "passive"))
      (node (ref "R19") (pin "1") (pinfunction "1_1") (pintype "passive"))
      (node (ref "R20") (pin "2") (pinfunction "2_2") (pintype "passive"))
    )
    (net (code "49") (name "Net-(IC9-SWE)") (class "Default")
      (node (ref "D4") (pin "C") (pinfunction "C_C") (pintype "passive"))
      (node (ref "IC9") (pin "2") (pinfunction "SWE_2") (pintype "passive"))
      (node (ref "L1") (pin "P$1") (pinfunction "1_P$1") (pintype "passive"))
    )
    (net (code "50") (name "Net-(IC9-TC)") (class "Default")
      (node (ref "C8") (pin "1") (pinfunction "1_1") (pintype "passive"))
      (node (ref "IC9") (pin "3") (pinfunction "TC_3") (pintype "passive"))
    )
    (net (code "51") (name "Net-(IC12-D)") (class "Default")
      (node (ref "IC12") (pin "3") (pinfunction "D_3") (pintype "power_in"))
      (node (ref "U$2") (pin "2") (pinfunction "AC2_2") (pintype "passive"))
    )
    (net (code "52") (name "Net-(IC12-G)") (class "Default")
      (node (ref "IC12") (pin "1") (pinfunction "G_1") (pintype "input"))
      (node (ref "R22") (pin "1") (pinfunction "1_1") (pintype "passive"))
    )
    (net (code "53") (name "Net-(LED1-PadA)") (class "Default")
      (node (ref "LED1") (pin "A") (pinfunction "A_A") (pintype "passive"))
      (node (ref "R13") (pin "2") (pinfunction "2_2") (pintype "passive"))
    )
    (net (code "54") (name "Net-(LED2-PadA)") (class "Default")
      (node (ref "LED2") (pin "A") (pinfunction "A_A") (pintype "passive"))
      (node (ref "R14") (pin "2") (pinfunction "2_2") (pintype "passive"))
    )
    (net (code "55") (name "Net-(LED3-PadA)") (class "Default")
      (node (ref "LED3") (pin "A") (pinfunction "A_A") (pintype "passive"))
      (node (ref "R15") (pin "2") (pinfunction "2_2") (pintype "passive"))
    )
    (net (code "56") (name "Net-(Q1-GATE)") (class "Default")
      (node (ref "Q1") (pin "4") (pinfunction "GATE_4") (pintype "passive"))
      (node (ref "R1") (pin "2") (pinfunction "2_2") (pintype "passive"))
    )
    (net (code "57") (name "Net-(Q2-GATE)") (class "Default")
      (node (ref "Q2") (pin "4") (pinfunction "GATE_4") (pintype "passive"))
      (node (ref "R3") (pin "2") (pinfunction "2_2") (pintype "passive"))
    )
    (net (code "58") (name "Net-(Q3-GATE)") (class "Default")
      (node (ref "Q3") (pin "4") (pinfunction "GATE_4") (pintype "passive"))
      (node (ref "R5") (pin "2") (pinfunction "2_2") (pintype "passive"))
    )
    (net (code "59") (name "Net-(Q4-GATE)") (class "Default")
      (node (ref "Q4") (pin "4") (pinfunction "GATE_4") (pintype "passive"))
      (node (ref "R2") (pin "2") (pinfunction "2_2") (pintype "passive"))
    )
    (net (code "60") (name "Net-(Q4-SOURCE-Pad1)") (class "Default")
      (node (ref "Q4") (pin "1") (pinfunction "SOURCE_1") (pintype "passive"))
      (node (ref "Q4") (pin "2") (pinfunction "SOURCE_2") (pintype "passive"))
      (node (ref "Q4") (pin "3") (pinfunction "SOURCE_3") (pintype "passive"))
      (node (ref "Q5") (pin "1") (pinfunction "SOURCE_1") (pintype "passive"))
      (node (ref "Q5") (pin "2") (pinfunction "SOURCE_2") (pintype "passive"))
      (node (ref "Q5") (pin "3") (pinfunction "SOURCE_3") (pintype "passive"))
      (node (ref "Q6") (pin "1") (pinfunction "SOURCE_1") (pintype "passive"))
      (node (ref "Q6") (pin "2") (pinfunction "SOURCE_2") (pintype "passive"))
      (node (ref "Q6") (pin "3") (pinfunction "SOURCE_3") (pintype "passive"))
      (node (ref "R10") (pin "2") (pinfunction "2_2") (pintype "passive"))
      (node (ref "R12") (pin "2") (pinfunction "2_2") (pintype "passive"))
      (node (ref "R28") (pin "2$1") (pinfunction "2_2$1") (pintype "passive"))
      (node (ref "R28") (pin "2$2") (pinfunction "2_2$2") (pintype "passive"))
      (node (ref "R8") (pin "2") (pinfunction "2_2") (pintype "passive"))
    )
    (net (code "61") (name "Net-(Q5-GATE)") (class "Default")
      (node (ref "Q5") (pin "4") (pinfunction "GATE_4") (pintype "passive"))
      (node (ref "R4") (pin "2") (pinfunction "2_2") (pintype "passive"))
    )
    (net (code "62") (name "Net-(Q6-GATE)") (class "Default")
      (node (ref "Q6") (pin "4") (pinfunction "GATE_4") (pintype "passive"))
      (node (ref "R6") (pin "2") (pinfunction "2_2") (pintype "passive"))
    )
    (net (code "63") (name "Net-(R22-Pad2)") (class "Default")
      (node (ref "R22") (pin "2") (pinfunction "2_2") (pintype "passive"))
      (node (ref "R23") (pin "2") (pinfunction "2_2") (pintype "passive"))
      (node (ref "X1") (pin "6") (pinfunction "6_6") (pintype "input"))
    )
    (net (code "64") (name "Net-(U$2-AC1)") (class "Default")
      (node (ref "R25") (pin "1") (pinfunction "1_1") (pintype "passive"))
      (node (ref "U$2") (pin "1") (pinfunction "AC1_1") (pintype "passive"))
    )
    (net (code "65") (name "Net-(U$5-IN+)") (class "Default")
      (node (ref "R28") (pin "2S") (pinfunction "2S_2S") (pintype "passive"))
      (node (ref "U$5") (pin "4") (pinfunction "IN+_4") (pintype "passive"))
    )
    (net (code "66") (name "Net-(U$5-IN-)") (class "Default")
      (node (ref "R28") (pin "1S") (pinfunction "1S_1S") (pintype "passive"))
      (node (ref "U$5") (pin "5") (pinfunction "IN-_5") (pintype "passive"))
    )
    (net (code "67") (name "Net-(U$5-OUT)") (class "Default")
      (node (ref "R29") (pin "1") (pinfunction "1_1") (pintype "passive"))
      (node (ref "U$5") (pin "6") (pinfunction "OUT_6") (pintype "passive"))
    )
    (net (code "68") (name "Net-(X1-A-G)") (class "Default")
      (node (ref "R26") (pin "1") (pinfunction "1_1") (pintype "passive"))
      (node (ref "X1") (pin "GA") (pinfunction "A-G_GA") (pintype "passive"))
    )
    (net (code "69") (name "Net-(X1-A-Y)") (class "Default")
      (node (ref "R27") (pin "1") (pinfunction "1_1") (pintype "passive"))
      (node (ref "X1") (pin "YA") (pinfunction "A-Y_YA") (pintype "passive"))
    )
    (net (code "70") (name "SWCLK") (class "Default")
      (node (ref "IC1") (pin "37") (pinfunction "PA14-JTCK-SWCLK_37") (pintype "bidirectional"))
      (node (ref "U$8") (pin "4") (pinfunction "4_4") (pintype "passive"))
    )
    (net (code "71") (name "SWDIO") (class "Default")
      (node (ref "IC1") (pin "34") (pinfunction "PA13-JTMS-SWDIO_34") (pintype "bidirectional"))
      (node (ref "U$8") (pin "6") (pinfunction "6_6") (pintype "passive"))
    )
    (net (code "72") (name "U") (class "Default")
      (node (ref "C2") (pin "2") (pinfunction "2_2") (pintype "passive"))
      (node (ref "IC2") (pin "13") (pinfunction "VS1_13") (pintype "bidirectional"))
      (node (ref "Q1") (pin "1") (pinfunction "SOURCE_1") (pintype "passive"))
      (node (ref "Q1") (pin "2") (pinfunction "SOURCE_2") (pintype "passive"))
      (node (ref "Q1") (pin "3") (pinfunction "SOURCE_3") (pintype "passive"))
      (node (ref "Q4") (pin "5") (pinfunction "DRAIN_5") (pintype "passive"))
      (node (ref "R7") (pin "2") (pinfunction "2_2") (pintype "passive"))
    )
    (net (code "73") (name "UART_RX") (class "Default")
      (node (ref "IC1") (pin "43") (pinfunction "PB7_43") (pintype "bidirectional"))
      (node (ref "U$8") (pin "1") (pinfunction "1_1") (pintype "passive"))
    )
    (net (code "74") (name "UART_TX") (class "Default")
      (node (ref "IC1") (pin "42") (pinfunction "PB6_42") (pintype "bidirectional"))
      (node (ref "U$8") (pin "3") (pinfunction "3_3") (pintype "passive"))
    )
    (net (code "75") (name "V") (class "Default")
      (node (ref "C1") (pin "2") (pinfunction "2_2") (pintype "passive"))
      (node (ref "IC2") (pin "17") (pinfunction "VS2_17") (pintype "bidirectional"))
      (node (ref "Q2") (pin "1") (pinfunction "SOURCE_1") (pintype "passive"))
      (node (ref "Q2") (pin "2") (pinfunction "SOURCE_2") (pintype "passive"))
      (node (ref "Q2") (pin "3") (pinfunction "SOURCE_3") (pintype "passive"))
      (node (ref "Q5") (pin "5") (pinfunction "DRAIN_5") (pintype "passive"))
      (node (ref "R9") (pin "2") (pinfunction "2_2") (pintype "passive"))
    )
    (net (code "76") (name "VCC") (class "Default")
      (node (ref "C11") (pin "+") (pinfunction "+_+") (pintype "passive"))
      (node (ref "C13") (pin "+") (pinfunction "+_+") (pintype "passive"))
      (node (ref "IC8") (pin "1") (pinfunction "VI_1") (pintype "input"))
      (node (ref "IC9") (pin "6") (pinfunction "VCC_6") (pintype "passive"))
      (node (ref "Q1") (pin "5") (pinfunction "DRAIN_5") (pintype "passive"))
      (node (ref "Q2") (pin "5") (pinfunction "DRAIN_5") (pintype "passive"))
      (node (ref "Q3") (pin "5") (pinfunction "DRAIN_5") (pintype "passive"))
      (node (ref "R21") (pin "2") (pinfunction "2_2") (pintype "passive"))
      (node (ref "R30") (pin "2") (pinfunction "2_2") (pintype "passive"))
    )
    (net (code "77") (name "VSENSE") (class "Default")
      (node (ref "C19") (pin "1") (pinfunction "1_1") (pintype "passive"))
      (node (ref "IC1") (pin "15") (pinfunction "PA5_15") (pintype "bidirectional"))
      (node (ref "R30") (pin "1") (pinfunction "1_1") (pintype "passive"))
      (node (ref "R31") (pin "2") (pinfunction "2_2") (pintype "passive"))
    )
    (net (code "78") (name "W") (class "Default")
      (node (ref "C3") (pin "1") (pinfunction "1_1") (pintype "passive"))
      (node (ref "IC2") (pin "8") (pinfunction "VS3_8") (pintype "bidirectional"))
      (node (ref "Q3") (pin "1") (pinfunction "SOURCE_1") (pintype "passive"))
      (node (ref "Q3") (pin "2") (pinfunction "SOURCE_2") (pintype "passive"))
      (node (ref "Q3") (pin "3") (pinfunction "SOURCE_3") (pintype "passive"))
      (node (ref "Q6") (pin "5") (pinfunction "DRAIN_5") (pintype "passive"))
      (node (ref "R11") (pin "2") (pinfunction "2_2") (pintype "passive"))
    )
    (net (code "79") (name "unconnected-(IC1-PA10-Pad31)") (class "Default")
      (node (ref "IC1") (pin "31") (pinfunction "PA10_31") (pintype "bidirectional"))
    )
    (net (code "80") (name "unconnected-(IC1-PA12-Pad33)") (class "Default")
      (node (ref "IC1") (pin "33") (pinfunction "PA12_33") (pintype "bidirectional"))
    )
    (net (code "81") (name "unconnected-(IC1-PA15-JTDI-Pad38)") (class "Default")
      (node (ref "IC1") (pin "38") (pinfunction "PA15-JTDI_38") (pintype "bidirectional"))
    )
    (net (code "82") (name "unconnected-(IC1-PB1-Pad19)") (class "Default")
      (node (ref "IC1") (pin "19") (pinfunction "PB1_19") (pintype "bidirectional"))
    )
    (net (code "83") (name "unconnected-(IC1-PB2-BOOT1-Pad20)") (class "Default")
      (node (ref "IC1") (pin "20") (pinfunction "PB2-BOOT1_20") (pintype "bidirectional"))
    )
    (net (code "84") (name "unconnected-(IC1-PB3-JTDO-Pad39)") (class "Default")
      (node (ref "IC1") (pin "39") (pinfunction "PB3-JTDO_39") (pintype "bidirectional"))
    )
    (net (code "85") (name "unconnected-(IC1-PB4-JNTRST-Pad40)") (class "Default")
      (node (ref "IC1") (pin "40") (pinfunction "PB4-JNTRST_40") (pintype "bidirectional"))
    )
    (net (code "86") (name "unconnected-(IC1-PB5-Pad41)") (class "Default")
      (node (ref "IC1") (pin "41") (pinfunction "PB5_41") (pintype "bidirectional"))
    )
    (net (code "87") (name "unconnected-(IC1-PB12-Pad25)") (class "Default")
      (node (ref "IC1") (pin "25") (pinfunction "PB12_25") (pintype "bidirectional"))
    )
    (net (code "88") (name "unconnected-(IC1-PC15-OSC32_OUT-Pad4)") (class "Default")
      (node (ref "IC1") (pin "4") (pinfunction "PC15-OSC32_OUT_4") (pintype "bidirectional"))
    )
    (net (code "89") (name "unconnected-(IC1-VBAT-Pad1)") (class "Default")
      (node (ref "IC1") (pin "1") (pinfunction "VBAT_1") (pintype "passive"))
    )
    (net (code "90") (name "~{EMS}") (class "Default")
      (node (ref "IC1") (pin "2") (pinfunction "PC13-TAMPER-RTC_2") (pintype "bidirectional"))
      (node (ref "IC4") (pin "1") (pinfunction "I0_1") (pintype "input"))
      (node (ref "IC5") (pin "1") (pinfunction "I0_1") (pintype "input"))
      (node (ref "IC6") (pin "1") (pinfunction "I0_1") (pintype "input"))
      (node (ref "R24") (pin "2") (pinfunction "2_2") (pintype "passive"))
      (node (ref "U$2") (pin "3") (pinfunction "E_3") (pintype "passive"))
    )
    (net (code "91") (name "~{RESET}") (class "Default")
      (node (ref "C7") (pin "1") (pinfunction "1_1") (pintype "passive"))
      (node (ref "IC1") (pin "7") (pinfunction "NRST_7") (pintype "bidirectional"))
      (node (ref "U$4") (pin "P$2") (pinfunction "2_P$2") (pintype "bidirectional"))
    )
  )
)
